# CanKnoten.net
KiCad netlist of a schematic drawn in EAGLE
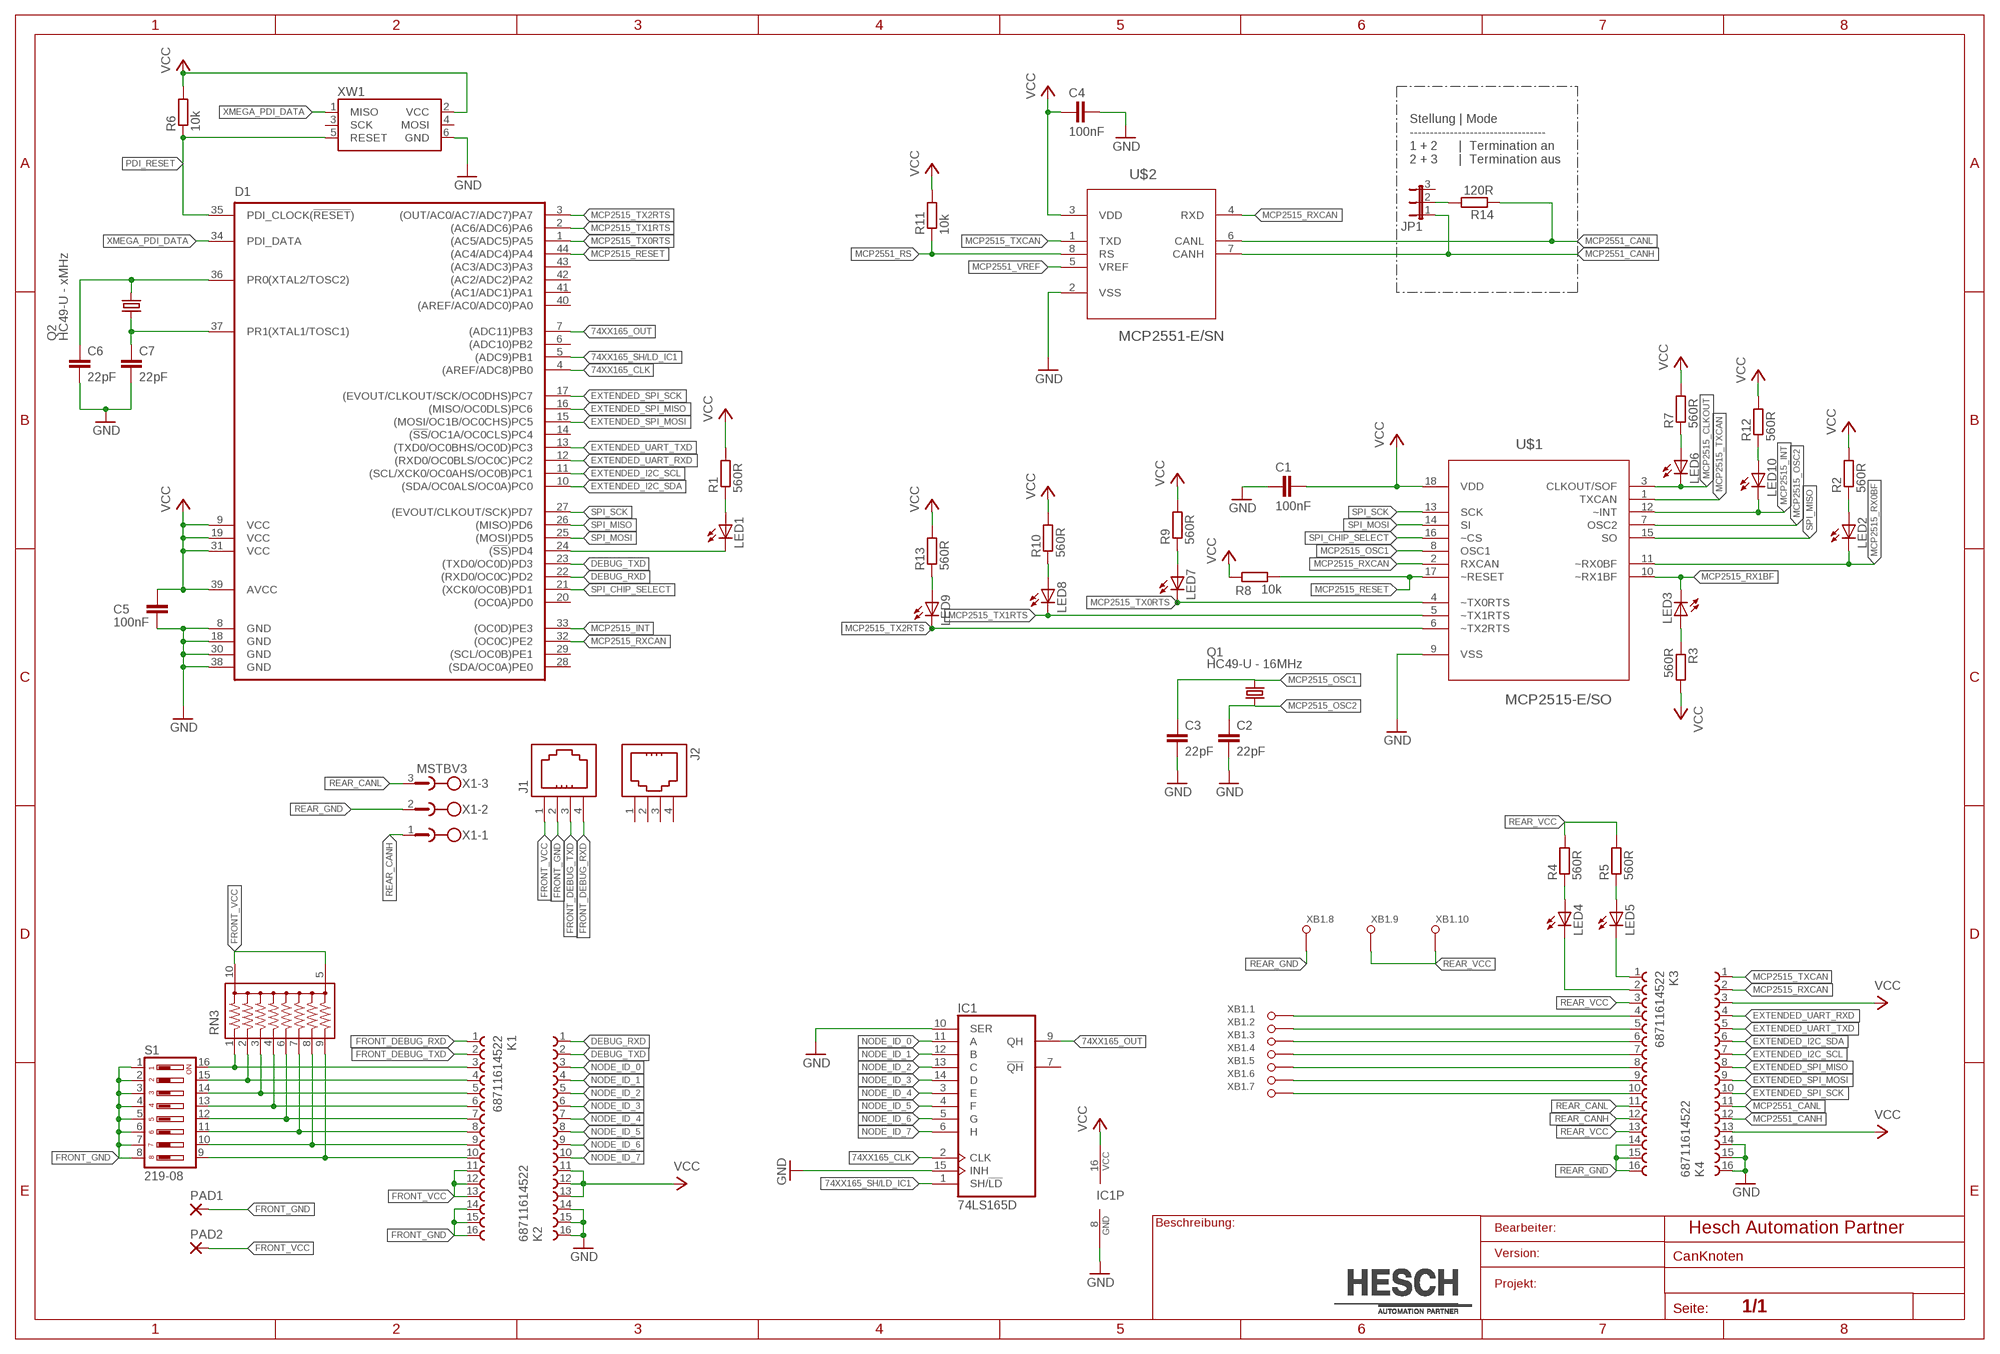
[diagram p0: schematic, sheet 1]

(export (version "E")
  (design (tool "Eeschema 10.0.6"))
  (components
    (comp (ref "C1")
      (value "100nF")
      (footprint "eagle-import:C1206")
      (libsource (lib "eagle-import") (part "C-EUC1206"))
    )
    (comp (ref "C2")
      (value "22pF")
      (footprint "eagle-import:C1206")
      (libsource (lib "eagle-import") (part "C-EUC1206"))
    )
    (comp (ref "C3")
      (value "22pF")
      (footprint "eagle-import:C1206")
      (libsource (lib "eagle-import") (part "C-EUC1206"))
    )
    (comp (ref "C4")
      (value "100nF")
      (footprint "eagle-import:C1206")
      (libsource (lib "eagle-import") (part "C-EUC1206"))
    )
    (comp (ref "C5")
      (value "100nF")
      (footprint "eagle-import:C1206")
      (libsource (lib "eagle-import") (part "C-EUC1206"))
    )
    (comp (ref "C6")
      (value "22pF")
      (footprint "eagle-import:C1206")
      (libsource (lib "eagle-import") (part "C-EUC1206"))
    )
    (comp (ref "C7")
      (value "22pF")
      (footprint "eagle-import:C1206")
      (libsource (lib "eagle-import") (part "C-EUC1206"))
    )
    (comp (ref "D1")
      (value "ATXMEGA16D4/32D4/64D4/128D4-A")
      (footprint "eagle-import:TQFP44A")
      (libsource (lib "eagle-import") (part "ATXMEGA16D4/32D4/64D4/128D4-A"))
    )
    (comp (ref "IC1")
      (value "74LS165D")
      (footprint "eagle-import:SO16")
      (libsource (lib "eagle-import") (part "74165DLS"))
    )
    (comp (ref "J1")
      (value "615004143821")
      (footprint "eagle-import:615004143821")
      (libsource (lib "eagle-import") (part "615004143821"))
    )
    (comp (ref "J2")
      (value "615004144021")
      (footprint "eagle-import:615004144021")
      (libsource (lib "eagle-import") (part "615004144021"))
    )
    (comp (ref "JP1")
      (value "JP2E")
      (footprint "eagle-import:JP2")
      (libsource (lib "eagle-import") (part "JP2E"))
    )
    (comp (ref "K1")
      (value "68711614522")
      (footprint "eagle-import:68711614522")
      (libsource (lib "eagle-import") (part "68711614522"))
    )
    (comp (ref "K2")
      (value "68711614522")
      (footprint "eagle-import:68711614522")
      (libsource (lib "eagle-import") (part "68711614522"))
    )
    (comp (ref "K3")
      (value "68711614522")
      (footprint "eagle-import:68711614522")
      (libsource (lib "eagle-import") (part "68711614522"))
    )
    (comp (ref "K4")
      (value "68711614522")
      (footprint "eagle-import:68711614522")
      (libsource (lib "eagle-import") (part "68711614522"))
    )
    (comp (ref "LED1")
      (value "LEDSML1206")
      (footprint "eagle-import:SML1206")
      (libsource (lib "eagle-import") (part "LEDSML1206"))
    )
    (comp (ref "LED2")
      (value "LEDSML1206")
      (footprint "eagle-import:SML1206")
      (libsource (lib "eagle-import") (part "LEDSML1206"))
    )
    (comp (ref "LED3")
      (value "LEDSML1206")
      (footprint "eagle-import:SML1206")
      (libsource (lib "eagle-import") (part "LEDSML1206"))
    )
    (comp (ref "LED4")
      (value "LEDSML1206")
      (footprint "eagle-import:SML1206")
      (libsource (lib "eagle-import") (part "LEDSML1206"))
    )
    (comp (ref "LED5")
      (value "LEDSML1206")
      (footprint "eagle-import:SML1206")
      (libsource (lib "eagle-import") (part "LEDSML1206"))
    )
    (comp (ref "LED6")
      (value "LEDSML1206")
      (footprint "eagle-import:SML1206")
      (libsource (lib "eagle-import") (part "LEDSML1206"))
    )
    (comp (ref "LED7")
      (value "LEDSML1206")
      (footprint "eagle-import:SML1206")
      (libsource (lib "eagle-import") (part "LEDSML1206"))
    )
    (comp (ref "LED8")
      (value "LEDSML1206")
      (footprint "eagle-import:SML1206")
      (libsource (lib "eagle-import") (part "LEDSML1206"))
    )
    (comp (ref "LED9")
      (value "LEDSML1206")
      (footprint "eagle-import:SML1206")
      (libsource (lib "eagle-import") (part "LEDSML1206"))
    )
    (comp (ref "LED10")
      (value "LEDSML1206")
      (footprint "eagle-import:SML1206")
      (libsource (lib "eagle-import") (part "LEDSML1206"))
    )
    (comp (ref "PAD1")
      (value "SMD5")
      (footprint "eagle-import:SMD2,54-5,08")
      (libsource (lib "eagle-import") (part "SMD5"))
    )
    (comp (ref "PAD2")
      (value "SMD5")
      (footprint "eagle-import:SMD2,54-5,08")
      (libsource (lib "eagle-import") (part "SMD5"))
    )
    (comp (ref "Q1")
      (value "HC49-U - 16MHz")
      (footprint "eagle-import:HC49")
      (libsource (lib "eagle-import") (part "HC49-U"))
    )
    (comp (ref "Q2")
      (value "HC49-U - xMHz")
      (footprint "eagle-import:HC49")
      (libsource (lib "eagle-import") (part "HC49-U"))
    )
    (comp (ref "R1")
      (value "560R")
      (footprint "eagle-import:R1206")
      (libsource (lib "eagle-import") (part "R-EU_R1206"))
    )
    (comp (ref "R2")
      (value "560R")
      (footprint "eagle-import:R1206")
      (libsource (lib "eagle-import") (part "R-EU_R1206"))
    )
    (comp (ref "R3")
      (value "560R")
      (footprint "eagle-import:R1206")
      (libsource (lib "eagle-import") (part "R-EU_R1206"))
    )
    (comp (ref "R4")
      (value "560R")
      (footprint "eagle-import:R1206")
      (libsource (lib "eagle-import") (part "R-EU_R1206"))
    )
    (comp (ref "R5")
      (value "560R")
      (footprint "eagle-import:R1206")
      (libsource (lib "eagle-import") (part "R-EU_R1206"))
    )
    (comp (ref "R6")
      (value "10k")
      (footprint "eagle-import:R1206")
      (libsource (lib "eagle-import") (part "R-EU_R1206"))
    )
    (comp (ref "R7")
      (value "560R")
      (footprint "eagle-import:R1206")
      (libsource (lib "eagle-import") (part "R-EU_R1206"))
    )
    (comp (ref "R8")
      (value "10k")
      (footprint "eagle-import:R1206")
      (libsource (lib "eagle-import") (part "R-EU_R1206"))
    )
    (comp (ref "R9")
      (value "560R")
      (footprint "eagle-import:R1206")
      (libsource (lib "eagle-import") (part "R-EU_R1206"))
    )
    (comp (ref "R10")
      (value "560R")
      (footprint "eagle-import:R1206")
      (libsource (lib "eagle-import") (part "R-EU_R1206"))
    )
    (comp (ref "R11")
      (value "10k")
      (footprint "eagle-import:R1206")
      (libsource (lib "eagle-import") (part "R-EU_R1206"))
    )
    (comp (ref "R12")
      (value "560R")
      (footprint "eagle-import:R1206")
      (libsource (lib "eagle-import") (part "R-EU_R1206"))
    )
    (comp (ref "R13")
      (value "560R")
      (footprint "eagle-import:R1206")
      (libsource (lib "eagle-import") (part "R-EU_R1206"))
    )
    (comp (ref "R14")
      (value "120R")
      (footprint "eagle-import:R1206")
      (libsource (lib "eagle-import") (part "R-EU_R1206"))
    )
    (comp (ref "RN3")
      (value "745-10")
      (footprint "eagle-import:745-10")
      (libsource (lib "eagle-import") (part "745-10"))
    )
    (comp (ref "S1")
      (value "219-08")
      (footprint "eagle-import:CTS-219-08")
      (libsource (lib "eagle-import") (part "219-08"))
    )
    (comp (ref "U$1")
      (value "MCP2515-E/SO")
      (footprint "eagle-import:SOIC127P1030X265-18N")
      (libsource (lib "eagle-import") (part "MCP2515-E/SO"))
    )
    (comp (ref "U$2")
      (value "MCP2551-E/SN")
      (footprint "eagle-import:SOIC127P600X175-8N")
      (libsource (lib "eagle-import") (part "MCP2551-E/SN"))
    )
    (comp (ref "X1")
      (value "MSTBV3")
      (footprint "eagle-import:MSTBV3")
      (fields (field (name "MPN") "MSTBV 2,5/3-GF-5.08"))
      (libsource (lib "eagle-import") (part "MSTBV3"))
    )
    (comp (ref "XB1")
      (value "WSL10")
      (footprint "eagle-import:WSL10")
      (libsource (lib "eagle-import") (part "WSL10"))
    )
    (comp (ref "XW1")
      (value "WSL6")
      (footprint "eagle-import:WSL")
      (libsource (lib "eagle-import") (part "WSL6"))
    )
  )
  (nets
    (net (code "1") (name "74XX165_CLK") (class "Default")
      (node (ref "D1") (pin "4") (pinfunction "(AREF/ADC8)PB0_4") (pintype "bidirectional"))
      (node (ref "IC1") (pin "2") (pinfunction "CLK_2") (pintype "input"))
    )
    (net (code "2") (name "74XX165_OUT") (class "Default")
      (node (ref "D1") (pin "7") (pinfunction "(ADC11)PB3_7") (pintype "bidirectional"))
      (node (ref "IC1") (pin "9") (pinfunction "QH_9") (pintype "output"))
    )
    (net (code "3") (name "74XX165_SH{slash}LD_IC1") (class "Default")
      (node (ref "D1") (pin "5") (pinfunction "(ADC9)PB1_5") (pintype "bidirectional"))
      (node (ref "IC1") (pin "1") (pinfunction "SH/~{LD}_1") (pintype "input"))
    )
    (net (code "4") (name "DEBUG_RXD") (class "Default")
      (node (ref "D1") (pin "22") (pinfunction "(RXD0/OC0C)PD2_22") (pintype "bidirectional"))
      (node (ref "K2") (pin "1") (pinfunction "1_1") (pintype "passive"))
    )
    (net (code "5") (name "DEBUG_TXD") (class "Default")
      (node (ref "D1") (pin "23") (pinfunction "(TXD0/OC0D)PD3_23") (pintype "bidirectional"))
      (node (ref "K2") (pin "2") (pinfunction "2_2") (pintype "passive"))
    )
    (net (code "6") (name "EXTENDED_I2C_SCL") (class "Default")
      (node (ref "D1") (pin "11") (pinfunction "(SCL/XCK0/OC0AHS/OC0B)PC1_11") (pintype "bidirectional"))
      (node (ref "K4") (pin "7") (pinfunction "7_7") (pintype "passive"))
    )
    (net (code "7") (name "EXTENDED_I2C_SDA") (class "Default")
      (node (ref "D1") (pin "10") (pinfunction "(SDA/OC0ALS/OC0A)PC0_10") (pintype "bidirectional"))
      (node (ref "K4") (pin "6") (pinfunction "6_6") (pintype "passive"))
    )
    (net (code "8") (name "EXTENDED_SPI_MISO") (class "Default")
      (node (ref "D1") (pin "16") (pinfunction "(MISO/OC0DLS)PC6_16") (pintype "bidirectional"))
      (node (ref "K4") (pin "8") (pinfunction "8_8") (pintype "passive"))
    )
    (net (code "9") (name "EXTENDED_SPI_MOSI") (class "Default")
      (node (ref "D1") (pin "15") (pinfunction "(MOSI/OC1B/OC0CHS)PC5_15") (pintype "bidirectional"))
      (node (ref "K4") (pin "9") (pinfunction "9_9") (pintype "passive"))
    )
    (net (code "10") (name "EXTENDED_SPI_SCK") (class "Default")
      (node (ref "D1") (pin "17") (pinfunction "(EVOUT/CLKOUT/SCK/OC0DHS)PC7_17") (pintype "bidirectional"))
      (node (ref "K4") (pin "10") (pinfunction "10_10") (pintype "passive"))
    )
    (net (code "11") (name "EXTENDED_UART_RXD") (class "Default")
      (node (ref "D1") (pin "12") (pinfunction "(RXD0/OC0BLS/OC0C)PC2_12") (pintype "bidirectional"))
      (node (ref "K4") (pin "4") (pinfunction "4_4") (pintype "passive"))
    )
    (net (code "12") (name "EXTENDED_UART_TXD") (class "Default")
      (node (ref "D1") (pin "13") (pinfunction "(TXD0/OC0BHS/OC0D)PC3_13") (pintype "bidirectional"))
      (node (ref "K4") (pin "5") (pinfunction "5_5") (pintype "passive"))
    )
    (net (code "13") (name "FRONT_DEBUG_RXD") (class "Default")
      (node (ref "J1") (pin "4") (pinfunction "1_4") (pintype "passive"))
      (node (ref "K1") (pin "1") (pinfunction "1_1") (pintype "passive"))
    )
    (net (code "14") (name "FRONT_DEBUG_TXD") (class "Default")
      (node (ref "J1") (pin "3") (pinfunction "2_3") (pintype "passive"))
      (node (ref "K1") (pin "2") (pinfunction "2_2") (pintype "passive"))
    )
    (net (code "15") (name "FRONT_GND") (class "Default")
      (node (ref "J1") (pin "2") (pinfunction "3_2") (pintype "passive"))
      (node (ref "K1") (pin "14") (pinfunction "14_14") (pintype "passive"))
      (node (ref "K1") (pin "15") (pinfunction "15_15") (pintype "passive"))
      (node (ref "K1") (pin "16") (pinfunction "16_16") (pintype "passive"))
      (node (ref "PAD1") (pin "1") (pinfunction "P_1") (pintype "passive"))
      (node (ref "S1") (pin "1") (pinfunction "1_1") (pintype "passive"))
      (node (ref "S1") (pin "2") (pinfunction "2_2") (pintype "passive"))
      (node (ref "S1") (pin "3") (pinfunction "3_3") (pintype "passive"))
      (node (ref "S1") (pin "4") (pinfunction "4_4") (pintype "passive"))
      (node (ref "S1") (pin "5") (pinfunction "5_5") (pintype "passive"))
      (node (ref "S1") (pin "6") (pinfunction "6_6") (pintype "passive"))
      (node (ref "S1") (pin "7") (pinfunction "7_7") (pintype "passive"))
      (node (ref "S1") (pin "8") (pinfunction "8_8") (pintype "passive"))
    )
    (net (code "16") (name "FRONT_VCC") (class "Default")
      (node (ref "J1") (pin "1") (pinfunction "4_1") (pintype "passive"))
      (node (ref "K1") (pin "11") (pinfunction "11_11") (pintype "passive"))
      (node (ref "K1") (pin "12") (pinfunction "12_12") (pintype "passive"))
      (node (ref "K1") (pin "13") (pinfunction "13_13") (pintype "passive"))
      (node (ref "PAD2") (pin "1") (pinfunction "P_1") (pintype "passive"))
      (node (ref "RN3") (pin "10") (pinfunction "10_10") (pintype "passive"))
      (node (ref "RN3") (pin "5") (pinfunction "5_5") (pintype "passive"))
    )
    (net (code "17") (name "GND") (class "Default")
      (node (ref "C1") (pin "2") (pinfunction "2_2") (pintype "passive"))
      (node (ref "C2") (pin "2") (pinfunction "2_2") (pintype "passive"))
      (node (ref "C3") (pin "2") (pinfunction "2_2") (pintype "passive"))
      (node (ref "C4") (pin "1") (pinfunction "1_1") (pintype "passive"))
      (node (ref "C5") (pin "2") (pinfunction "2_2") (pintype "passive"))
      (node (ref "C6") (pin "2") (pinfunction "2_2") (pintype "passive"))
      (node (ref "C7") (pin "2") (pinfunction "2_2") (pintype "passive"))
      (node (ref "D1") (pin "18") (pinfunction "GND_18") (pintype "power_in"))
      (node (ref "D1") (pin "30") (pinfunction "GND_30") (pintype "power_in"))
      (node (ref "D1") (pin "38") (pinfunction "GND_38") (pintype "power_in"))
      (node (ref "D1") (pin "8") (pinfunction "GND_8") (pintype "power_in"))
      (node (ref "IC1") (pin "10") (pinfunction "SER_10") (pintype "input"))
      (node (ref "IC1") (pin "15") (pinfunction "INH_15") (pintype "input"))
      (node (ref "IC1") (pin "8") (pinfunction "GND_8") (pintype "power_in"))
      (node (ref "K2") (pin "14") (pinfunction "14_14") (pintype "passive"))
      (node (ref "K2") (pin "15") (pinfunction "15_15") (pintype "passive"))
      (node (ref "K2") (pin "16") (pinfunction "16_16") (pintype "passive"))
      (node (ref "K4") (pin "14") (pinfunction "14_14") (pintype "passive"))
      (node (ref "K4") (pin "15") (pinfunction "15_15") (pintype "passive"))
      (node (ref "K4") (pin "16") (pinfunction "16_16") (pintype "passive"))
      (node (ref "U$1") (pin "9") (pinfunction "VSS_9") (pintype "power_in"))
      (node (ref "U$2") (pin "2") (pinfunction "VSS_2") (pintype "power_in"))
      (node (ref "XW1") (pin "6") (pinfunction "GND_6") (pintype "power_in"))
    )
    (net (code "18") (name "MCP2515_CLKOUT") (class "Default")
      (node (ref "LED6") (pin "C") (pinfunction "C_C") (pintype "passive"))
      (node (ref "U$1") (pin "3") (pinfunction "CLKOUT/SOF_3") (pintype "output"))
    )
    (net (code "19") (name "MCP2515_INT") (class "Default")
      (node (ref "D1") (pin "33") (pinfunction "(OC0D)PE3_33") (pintype "bidirectional"))
      (node (ref "LED10") (pin "C") (pinfunction "C_C") (pintype "passive"))
      (node (ref "U$1") (pin "12") (pinfunction "~{INT}_12") (pintype "output"))
    )
    (net (code "20") (name "MCP2515_OSC1") (class "Default")
      (node (ref "C3") (pin "1") (pinfunction "1_1") (pintype "passive"))
      (node (ref "Q1") (pin "2") (pinfunction "2_2") (pintype "passive"))
      (node (ref "U$1") (pin "8") (pinfunction "OSC1_8") (pintype "input"))
    )
    (net (code "21") (name "MCP2515_OSC2") (class "Default")
      (node (ref "C2") (pin "1") (pinfunction "1_1") (pintype "passive"))
      (node (ref "Q1") (pin "1") (pinfunction "1_1") (pintype "passive"))
      (node (ref "U$1") (pin "7") (pinfunction "OSC2_7") (pintype "output"))
    )
    (net (code "22") (name "MCP2515_RESET") (class "Default")
      (node (ref "D1") (pin "44") (pinfunction "(AC4/ADC4)PA4_44") (pintype "bidirectional"))
      (node (ref "R8") (pin "1") (pinfunction "1_1") (pintype "passive"))
      (node (ref "U$1") (pin "17") (pinfunction "~{RESET}_17") (pintype "input"))
    )
    (net (code "23") (name "MCP2515_RX0BF") (class "Default")
      (node (ref "LED2") (pin "C") (pinfunction "C_C") (pintype "passive"))
      (node (ref "U$1") (pin "11") (pinfunction "~{RX0BF}_11") (pintype "output"))
    )
    (net (code "24") (name "MCP2515_RX1BF") (class "Default")
      (node (ref "LED3") (pin "C") (pinfunction "C_C") (pintype "passive"))
      (node (ref "U$1") (pin "10") (pinfunction "~{RX1BF}_10") (pintype "output"))
    )
    (net (code "25") (name "MCP2515_RXCAN") (class "Default")
      (node (ref "D1") (pin "32") (pinfunction "(OC0C)PE2_32") (pintype "bidirectional"))
      (node (ref "K4") (pin "2") (pinfunction "2_2") (pintype "passive"))
      (node (ref "U$1") (pin "2") (pinfunction "RXCAN_2") (pintype "input"))
      (node (ref "U$2") (pin "4") (pinfunction "RXD_4") (pintype "output"))
    )
    (net (code "26") (name "MCP2515_TX0RTS") (class "Default")
      (node (ref "D1") (pin "1") (pinfunction "(AC5/ADC5)PA5_1") (pintype "bidirectional"))
      (node (ref "LED7") (pin "C") (pinfunction "C_C") (pintype "passive"))
      (node (ref "U$1") (pin "4") (pinfunction "~{TX0RTS}_4") (pintype "input"))
    )
    (net (code "27") (name "MCP2515_TX1RTS") (class "Default")
      (node (ref "D1") (pin "2") (pinfunction "(AC6/ADC6)PA6_2") (pintype "bidirectional"))
      (node (ref "LED8") (pin "C") (pinfunction "C_C") (pintype "passive"))
      (node (ref "U$1") (pin "5") (pinfunction "~{TX1RTS}_5") (pintype "input"))
    )
    (net (code "28") (name "MCP2515_TX2RTS") (class "Default")
      (node (ref "D1") (pin "3") (pinfunction "(OUT/AC0/AC7/ADC7)PA7_3") (pintype "bidirectional"))
      (node (ref "LED9") (pin "C") (pinfunction "C_C") (pintype "passive"))
      (node (ref "U$1") (pin "6") (pinfunction "~{TX2RTS}_6") (pintype "input"))
    )
    (net (code "29") (name "MCP2515_TXCAN") (class "Default")
      (node (ref "K4") (pin "1") (pinfunction "1_1") (pintype "passive"))
      (node (ref "U$1") (pin "1") (pinfunction "TXCAN_1") (pintype "output"))
      (node (ref "U$2") (pin "1") (pinfunction "TXD_1") (pintype "input"))
    )
    (net (code "30") (name "MCP2551_CANH") (class "Default")
      (node (ref "JP1") (pin "1") (pinfunction "1_1") (pintype "passive"))
      (node (ref "K4") (pin "12") (pinfunction "12_12") (pintype "passive"))
      (node (ref "U$2") (pin "7") (pinfunction "CANH_7") (pintype "output"))
    )
    (net (code "31") (name "MCP2551_CANL") (class "Default")
      (node (ref "K4") (pin "11") (pinfunction "11_11") (pintype "passive"))
      (node (ref "R14") (pin "1") (pinfunction "1_1") (pintype "passive"))
      (node (ref "U$2") (pin "6") (pinfunction "CANL_6") (pintype "output"))
    )
    (net (code "32") (name "MCP2551_RS") (class "Default")
      (node (ref "R11") (pin "1") (pinfunction "1_1") (pintype "passive"))
      (node (ref "U$2") (pin "8") (pinfunction "RS_8") (pintype "input"))
    )
    (net (code "33") (name "MCP2551_VREF") (class "Default")
      (node (ref "U$2") (pin "5") (pinfunction "VREF_5") (pintype "input"))
    )
    (net (code "34") (name "NODE_ID_0") (class "Default")
      (node (ref "IC1") (pin "11") (pinfunction "A_11") (pintype "input"))
      (node (ref "K2") (pin "3") (pinfunction "3_3") (pintype "passive"))
    )
    (net (code "35") (name "NODE_ID_1") (class "Default")
      (node (ref "IC1") (pin "12") (pinfunction "B_12") (pintype "input"))
      (node (ref "K2") (pin "4") (pinfunction "4_4") (pintype "passive"))
    )
    (net (code "36") (name "NODE_ID_2") (class "Default")
      (node (ref "IC1") (pin "13") (pinfunction "C_13") (pintype "input"))
      (node (ref "K2") (pin "5") (pinfunction "5_5") (pintype "passive"))
    )
    (net (code "37") (name "NODE_ID_3") (class "Default")
      (node (ref "IC1") (pin "14") (pinfunction "D_14") (pintype "input"))
      (node (ref "K2") (pin "6") (pinfunction "6_6") (pintype "passive"))
    )
    (net (code "38") (name "NODE_ID_4") (class "Default")
      (node (ref "IC1") (pin "3") (pinfunction "E_3") (pintype "input"))
      (node (ref "K2") (pin "7") (pinfunction "7_7") (pintype "passive"))
    )
    (net (code "39") (name "NODE_ID_5") (class "Default")
      (node (ref "IC1") (pin "4") (pinfunction "F_4") (pintype "input"))
      (node (ref "K2") (pin "8") (pinfunction "8_8") (pintype "passive"))
    )
    (net (code "40") (name "NODE_ID_6") (class "Default")
      (node (ref "IC1") (pin "5") (pinfunction "G_5") (pintype "input"))
      (node (ref "K2") (pin "9") (pinfunction "9_9") (pintype "passive"))
    )
    (net (code "41") (name "NODE_ID_7") (class "Default")
      (node (ref "IC1") (pin "6") (pinfunction "H_6") (pintype "input"))
      (node (ref "K2") (pin "10") (pinfunction "10_10") (pintype "passive"))
    )
    (net (code "42") (name "Net-(D1-(~{SS})PD4)") (class "Default")
      (node (ref "D1") (pin "24") (pinfunction "(~{SS})PD4_24") (pintype "bidirectional"))
      (node (ref "LED1") (pin "C") (pinfunction "C_C") (pintype "passive"))
    )
    (net (code "43") (name "Net-(D1-PR0(XTAL2{slash}TOSC2))") (class "Default")
      (node (ref "C6") (pin "1") (pinfunction "1_1") (pintype "passive"))
      (node (ref "D1") (pin "36") (pinfunction "PR0(XTAL2/TOSC2)_36") (pintype "bidirectional"))
      (node (ref "Q2") (pin "2") (pinfunction "2_2") (pintype "passive"))
    )
    (net (code "44") (name "Net-(D1-PR1(XTAL1{slash}TOSC1))") (class "Default")
      (node (ref "C7") (pin "1") (pinfunction "1_1") (pintype "passive"))
      (node (ref "D1") (pin "37") (pinfunction "PR1(XTAL1/TOSC1)_37") (pintype "bidirectional"))
      (node (ref "Q2") (pin "1") (pinfunction "1_1") (pintype "passive"))
    )
    (net (code "45") (name "Net-(JP1-Pad2)") (class "Default")
      (node (ref "JP1") (pin "2") (pinfunction "2_2") (pintype "passive"))
      (node (ref "R14") (pin "2") (pinfunction "2_2") (pintype "passive"))
    )
    (net (code "46") (name "Net-(K1-Pad3)") (class "Default")
      (node (ref "K1") (pin "3") (pinfunction "3_3") (pintype "passive"))
      (node (ref "RN3") (pin "1") (pinfunction "1_1") (pintype "passive"))
      (node (ref "S1") (pin "16") (pinfunction "16_16") (pintype "passive"))
    )
    (net (code "47") (name "Net-(K1-Pad4)") (class "Default")
      (node (ref "K1") (pin "4") (pinfunction "4_4") (pintype "passive"))
      (node (ref "RN3") (pin "2") (pinfunction "2_2") (pintype "passive"))
      (node (ref "S1") (pin "15") (pinfunction "15_15") (pintype "passive"))
    )
    (net (code "48") (name "Net-(K1-Pad5)") (class "Default")
      (node (ref "K1") (pin "5") (pinfunction "5_5") (pintype "passive"))
      (node (ref "RN3") (pin "3") (pinfunction "3_3") (pintype "passive"))
      (node (ref "S1") (pin "14") (pinfunction "14_14") (pintype "passive"))
    )
    (net (code "49") (name "Net-(K1-Pad6)") (class "Default")
      (node (ref "K1") (pin "6") (pinfunction "6_6") (pintype "passive"))
      (node (ref "RN3") (pin "4") (pinfunction "4_4") (pintype "passive"))
      (node (ref "S1") (pin "13") (pinfunction "13_13") (pintype "passive"))
    )
    (net (code "50") (name "Net-(K1-Pad7)") (class "Default")
      (node (ref "K1") (pin "7") (pinfunction "7_7") (pintype "passive"))
      (node (ref "RN3") (pin "6") (pinfunction "6_6") (pintype "passive"))
      (node (ref "S1") (pin "12") (pinfunction "12_12") (pintype "passive"))
    )
    (net (code "51") (name "Net-(K1-Pad8)") (class "Default")
      (node (ref "K1") (pin "8") (pinfunction "8_8") (pintype "passive"))
      (node (ref "RN3") (pin "7") (pinfunction "7_7") (pintype "passive"))
      (node (ref "S1") (pin "11") (pinfunction "11_11") (pintype "passive"))
    )
    (net (code "52") (name "Net-(K1-Pad9)") (class "Default")
      (node (ref "K1") (pin "9") (pinfunction "9_9") (pintype "passive"))
      (node (ref "RN3") (pin "8") (pinfunction "8_8") (pintype "passive"))
      (node (ref "S1") (pin "10") (pinfunction "10_10") (pintype "passive"))
    )
    (net (code "53") (name "Net-(K1-Pad10)") (class "Default")
      (node (ref "K1") (pin "10") (pinfunction "10_10") (pintype "passive"))
      (node (ref "RN3") (pin "9") (pinfunction "9_9") (pintype "passive"))
      (node (ref "S1") (pin "9") (pinfunction "9_9") (pintype "passive"))
    )
    (net (code "54") (name "Net-(K3-Pad1)") (class "Default")
      (node (ref "K3") (pin "1") (pinfunction "1_1") (pintype "passive"))
      (node (ref "LED5") (pin "C") (pinfunction "C_C") (pintype "passive"))
    )
    (net (code "55") (name "Net-(K3-Pad2)") (class "Default")
      (node (ref "K3") (pin "2") (pinfunction "2_2") (pintype "passive"))
      (node (ref "LED4") (pin "C") (pinfunction "C_C") (pintype "passive"))
    )
    (net (code "56") (name "Net-(LED1-PadA)") (class "Default")
      (node (ref "LED1") (pin "A") (pinfunction "A_A") (pintype "passive"))
      (node (ref "R1") (pin "1") (pinfunction "1_1") (pintype "passive"))
    )
    (net (code "57") (name "Net-(LED2-PadA)") (class "Default")
      (node (ref "LED2") (pin "A") (pinfunction "A_A") (pintype "passive"))
      (node (ref "R2") (pin "1") (pinfunction "1_1") (pintype "passive"))
    )
    (net (code "58") (name "Net-(LED3-PadA)") (class "Default")
      (node (ref "LED3") (pin "A") (pinfunction "A_A") (pintype "passive"))
      (node (ref "R3") (pin "1") (pinfunction "1_1") (pintype "passive"))
    )
    (net (code "59") (name "Net-(LED4-PadA)") (class "Default")
      (node (ref "LED4") (pin "A") (pinfunction "A_A") (pintype "passive"))
      (node (ref "R4") (pin "1") (pinfunction "1_1") (pintype "passive"))
    )
    (net (code "60") (name "Net-(LED5-PadA)") (class "Default")
      (node (ref "LED5") (pin "A") (pinfunction "A_A") (pintype "passive"))
      (node (ref "R5") (pin "1") (pinfunction "1_1") (pintype "passive"))
    )
    (net (code "61") (name "Net-(LED6-PadA)") (class "Default")
      (node (ref "LED6") (pin "A") (pinfunction "A_A") (pintype "passive"))
      (node (ref "R7") (pin "1") (pinfunction "1_1") (pintype "passive"))
    )
    (net (code "62") (name "Net-(LED7-PadA)") (class "Default")
      (node (ref "LED7") (pin "A") (pinfunction "A_A") (pintype "passive"))
      (node (ref "R9") (pin "1") (pinfunction "1_1") (pintype "passive"))
    )
    (net (code "63") (name "Net-(LED8-PadA)") (class "Default")
      (node (ref "LED8") (pin "A") (pinfunction "A_A") (pintype "passive"))
      (node (ref "R10") (pin "1") (pinfunction "1_1") (pintype "passive"))
    )
    (net (code "64") (name "Net-(LED9-PadA)") (class "Default")
      (node (ref "LED9") (pin "A") (pinfunction "A_A") (pintype "passive"))
      (node (ref "R13") (pin "1") (pinfunction "1_1") (pintype "passive"))
    )
    (net (code "65") (name "Net-(LED10-PadA)") (class "Default")
      (node (ref "LED10") (pin "A") (pinfunction "A_A") (pintype "passive"))
      (node (ref "R12") (pin "1") (pinfunction "1_1") (pintype "passive"))
    )
    (net (code "66") (name "Net-(XB1A-.1)") (class "Default")
      (node (ref "K3") (pin "4") (pinfunction "4_4") (pintype "passive"))
      (node (ref "XB1") (pin "1") (pinfunction ".1_1") (pintype "bidirectional"))
    )
    (net (code "67") (name "Net-(XB1C-.1)") (class "Default")
      (node (ref "K3") (pin "5") (pinfunction "5_5") (pintype "passive"))
      (node (ref "XB1") (pin "2") (pinfunction ".1_2") (pintype "bidirectional"))
    )
    (net (code "68") (name "Net-(XB1D-.1)") (class "Default")
      (node (ref "K3") (pin "6") (pinfunction "6_6") (pintype "passive"))
      (node (ref "XB1") (pin "3") (pinfunction ".1_3") (pintype "bidirectional"))
    )
    (net (code "69") (name "Net-(XB1E-.1)") (class "Default")
      (node (ref "K3") (pin "7") (pinfunction "7_7") (pintype "passive"))
      (node (ref "XB1") (pin "4") (pinfunction ".1_4") (pintype "bidirectional"))
    )
    (net (code "70") (name "Net-(XB1F-.1)") (class "Default")
      (node (ref "K3") (pin "8") (pinfunction "8_8") (pintype "passive"))
      (node (ref "XB1") (pin "5") (pinfunction ".1_5") (pintype "bidirectional"))
    )
    (net (code "71") (name "Net-(XB1G-.1)") (class "Default")
      (node (ref "K3") (pin "9") (pinfunction "9_9") (pintype "passive"))
      (node (ref "XB1") (pin "6") (pinfunction ".1_6") (pintype "bidirectional"))
    )
    (net (code "72") (name "Net-(XB1H-.1)") (class "Default")
      (node (ref "K3") (pin "10") (pinfunction "10_10") (pintype "passive"))
      (node (ref "XB1") (pin "7") (pinfunction ".1_7") (pintype "bidirectional"))
    )
    (net (code "73") (name "PDI_RESET") (class "Default")
      (node (ref "D1") (pin "35") (pinfunction "PDI_CLOCK(~{RESET})_35") (pintype "input"))
      (node (ref "R6") (pin "1") (pinfunction "1_1") (pintype "passive"))
      (node (ref "XW1") (pin "5") (pinfunction "RESET_5") (pintype "bidirectional"))
    )
    (net (code "74") (name "REAR_CANH") (class "Default")
      (node (ref "K3") (pin "12") (pinfunction "12_12") (pintype "passive"))
      (node (ref "X1") (pin "1") (pinfunction "1_1") (pintype "passive"))
    )
    (net (code "75") (name "REAR_CANL") (class "Default")
      (node (ref "K3") (pin "11") (pinfunction "11_11") (pintype "passive"))
      (node (ref "X1") (pin "3") (pinfunction "1_3") (pintype "passive"))
    )
    (net (code "76") (name "REAR_GND") (class "Default")
      (node (ref "K3") (pin "14") (pinfunction "14_14") (pintype "passive"))
      (node (ref "K3") (pin "15") (pinfunction "15_15") (pintype "passive"))
      (node (ref "K3") (pin "16") (pinfunction "16_16") (pintype "passive"))
      (node (ref "X1") (pin "2") (pinfunction "1_2") (pintype "passive"))
      (node (ref "XB1") (pin "8") (pinfunction ".1_8") (pintype "bidirectional"))
    )
    (net (code "77") (name "REAR_VCC") (class "Default")
      (node (ref "K3") (pin "13") (pinfunction "13_13") (pintype "passive"))
      (node (ref "K3") (pin "3") (pinfunction "3_3") (pintype "passive"))
      (node (ref "R4") (pin "2") (pinfunction "2_2") (pintype "passive"))
      (node (ref "R5") (pin "2") (pinfunction "2_2") (pintype "passive"))
      (node (ref "XB1") (pin "10") (pinfunction ".1_10") (pintype "bidirectional"))
      (node (ref "XB1") (pin "9") (pinfunction ".1_9") (pintype "bidirectional"))
    )
    (net (code "78") (name "SPI_CHIP_SELECT") (class "Default")
      (node (ref "D1") (pin "21") (pinfunction "(XCK0/OC0B)PD1_21") (pintype "bidirectional"))
      (node (ref "U$1") (pin "16") (pinfunction "~{CS}_16") (pintype "input"))
    )
    (net (code "79") (name "SPI_MISO") (class "Default")
      (node (ref "D1") (pin "26") (pinfunction "(MISO)PD6_26") (pintype "bidirectional"))
      (node (ref "U$1") (pin "15") (pinfunction "SO_15") (pintype "output"))
    )
    (net (code "80") (name "SPI_MOSI") (class "Default")
      (node (ref "D1") (pin "25") (pinfunction "(MOSI)PD5_25") (pintype "bidirectional"))
      (node (ref "U$1") (pin "14") (pinfunction "SI_14") (pintype "input"))
    )
    (net (code "81") (name "SPI_SCK") (class "Default")
      (node (ref "D1") (pin "27") (pinfunction "(EVOUT/CLKOUT/SCK)PD7_27") (pintype "bidirectional"))
      (node (ref "U$1") (pin "13") (pinfunction "SCK_13") (pintype "input"))
    )
    (net (code "82") (name "VCC") (class "Default")
      (node (ref "C1") (pin "1") (pinfunction "1_1") (pintype "passive"))
      (node (ref "C4") (pin "2") (pinfunction "2_2") (pintype "passive"))
      (node (ref "C5") (pin "1") (pinfunction "1_1") (pintype "passive"))
      (node (ref "D1") (pin "19") (pinfunction "VCC_19") (pintype "power_in"))
      (node (ref "D1") (pin "31") (pinfunction "VCC_31") (pintype "power_in"))
      (node (ref "D1") (pin "39") (pinfunction "AVCC_39") (pintype "power_in"))
      (node (ref "D1") (pin "9") (pinfunction "VCC_9") (pintype "power_in"))
      (node (ref "IC1") (pin "16") (pinfunction "VCC_16") (pintype "power_in"))
      (node (ref "K2") (pin "11") (pinfunction "11_11") (pintype "passive"))
      (node (ref "K2") (pin "12") (pinfunction "12_12") (pintype "passive"))
      (node (ref "K2") (pin "13") (pinfunction "13_13") (pintype "passive"))
      (node (ref "K4") (pin "13") (pinfunction "13_13") (pintype "passive"))
      (node (ref "K4") (pin "3") (pinfunction "3_3") (pintype "passive"))
      (node (ref "R1") (pin "2") (pinfunction "2_2") (pintype "passive"))
      (node (ref "R10") (pin "2") (pinfunction "2_2") (pintype "passive"))
      (node (ref "R11") (pin "2") (pinfunction "2_2") (pintype "passive"))
      (node (ref "R12") (pin "2") (pinfunction "2_2") (pintype "passive"))
      (node (ref "R13") (pin "2") (pinfunction "2_2") (pintype "passive"))
      (node (ref "R2") (pin "2") (pinfunction "2_2") (pintype "passive"))
      (node (ref "R3") (pin "2") (pinfunction "2_2") (pintype "passive"))
      (node (ref "R6") (pin "2") (pinfunction "2_2") (pintype "passive"))
      (node (ref "R7") (pin "2") (pinfunction "2_2") (pintype "passive"))
      (node (ref "R8") (pin "2") (pinfunction "2_2") (pintype "passive"))
      (node (ref "R9") (pin "2") (pinfunction "2_2") (pintype "passive"))
      (node (ref "U$1") (pin "18") (pinfunction "VDD_18") (pintype "power_in"))
      (node (ref "U$2") (pin "3") (pinfunction "VDD_3") (pintype "power_in"))
      (node (ref "XW1") (pin "2") (pinfunction "VCC_2") (pintype "power_in"))
    )
    (net (code "83") (name "XMEGA_PDI_DATA") (class "Default")
      (node (ref "D1") (pin "34") (pinfunction "PDI_DATA_34") (pintype "bidirectional"))
      (node (ref "XW1") (pin "1") (pinfunction "MISO_1") (pintype "bidirectional"))
    )
    (net (code "84") (name "unconnected-(D1-(AC1{slash}ADC1)PA1-Pad41)") (class "Default")
      (node (ref "D1") (pin "41") (pinfunction "(AC1/ADC1)PA1_41") (pintype "bidirectional"))
    )
    (net (code "85") (name "unconnected-(D1-(AC2{slash}ADC2)PA2-Pad42)") (class "Default")
      (node (ref "D1") (pin "42") (pinfunction "(AC2/ADC2)PA2_42") (pintype "bidirectional"))
    )
    (net (code "86") (name "unconnected-(D1-(AC3{slash}ADC3)PA3-Pad43)") (class "Default")
      (node (ref "D1") (pin "43") (pinfunction "(AC3/ADC3)PA3_43") (pintype "bidirectional"))
    )
    (net (code "87") (name "unconnected-(D1-(ADC10)PB2-Pad6)") (class "Default")
      (node (ref "D1") (pin "6") (pinfunction "(ADC10)PB2_6") (pintype "bidirectional"))
    )
    (net (code "88") (name "unconnected-(D1-(AREF{slash}AC0{slash}ADC0)PA0-Pad40)") (class "Default")
      (node (ref "D1") (pin "40") (pinfunction "(AREF/AC0/ADC0)PA0_40") (pintype "bidirectional"))
    )
    (net (code "89") (name "unconnected-(D1-(OC0A)PD0-Pad20)") (class "Default")
      (node (ref "D1") (pin "20") (pinfunction "(OC0A)PD0_20") (pintype "bidirectional"))
    )
    (net (code "90") (name "unconnected-(D1-(SCL{slash}OC0B)PE1-Pad29)") (class "Default")
      (node (ref "D1") (pin "29") (pinfunction "(SCL/OC0B)PE1_29") (pintype "bidirectional"))
    )
    (net (code "91") (name "unconnected-(D1-(SDA{slash}OC0A)PE0-Pad28)") (class "Default")
      (node (ref "D1") (pin "28") (pinfunction "(SDA/OC0A)PE0_28") (pintype "bidirectional"))
    )
    (net (code "92") (name "unconnected-(D1-(~{SS}{slash}OC1A{slash}OC0CLS)PC4-Pad14)") (class "Default")
      (node (ref "D1") (pin "14") (pinfunction "(~{SS}/OC1A/OC0CLS)PC4_14") (pintype "bidirectional"))
    )
    (net (code "93") (name "unconnected-(IC1A-~{QH}-Pad7)") (class "Default")
      (node (ref "IC1") (pin "7") (pinfunction "~{QH}_7") (pintype "output"))
    )
    (net (code "94") (name "unconnected-(J2-Pad1)") (class "Default")
      (node (ref "J2") (pin "1") (pinfunction "1_1") (pintype "passive"))
    )
    (net (code "95") (name "unconnected-(J2-Pad2)") (class "Default")
      (node (ref "J2") (pin "2") (pinfunction "2_2") (pintype "passive"))
    )
    (net (code "96") (name "unconnected-(J2-Pad3)") (class "Default")
      (node (ref "J2") (pin "3") (pinfunction "3_3") (pintype "passive"))
    )
    (net (code "97") (name "unconnected-(J2-Pad4)") (class "Default")
      (node (ref "J2") (pin "4") (pinfunction "4_4") (pintype "passive"))
    )
    (net (code "98") (name "unconnected-(JP1-Pad3)") (class "Default")
      (node (ref "JP1") (pin "3") (pinfunction "3_3") (pintype "passive"))
    )
    (net (code "99") (name "unconnected-(XW1-MOSI-Pad4)") (class "Default")
      (node (ref "XW1") (pin "4") (pinfunction "MOSI_4") (pintype "bidirectional"))
    )
    (net (code "100") (name "unconnected-(XW1-SCK-Pad3)") (class "Default")
      (node (ref "XW1") (pin "3") (pinfunction "SCK_3") (pintype "bidirectional"))
    )
  )
)
